# VUE_PIC32_v1_0_PowerOut.net
KiCad netlist of a schematic drawn in Altium Designer
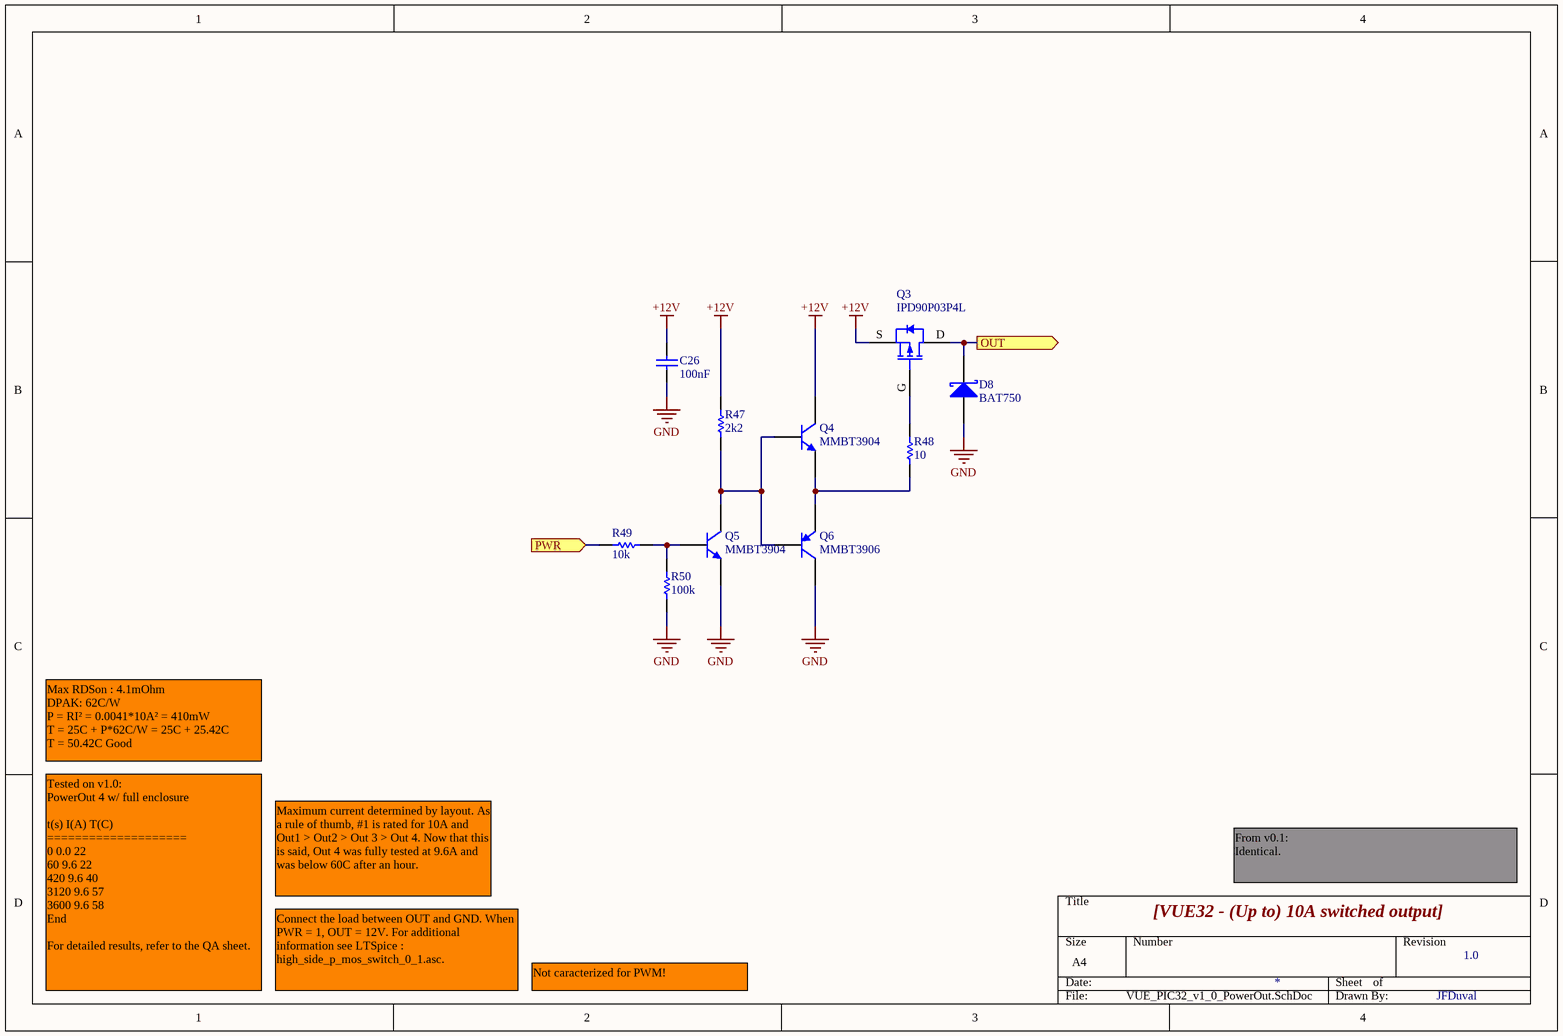
[diagram p0: VUE_PIC32_v1_0_PowerOut.SchDoc]

(export (version "E")
  (design (tool "Eeschema 10.0.6"))
  (components
    (comp (ref "C26")
      (value "100nF")
      (footprint "0402C")
      (description "CAP CER 0.1UF 25V Y5V 0402")
      (fields (field (name "MFG") "TDK") (field (name "MFGPARTNUMBER") "C1005Y5V1E104Z"))
      (libsource (lib "JFD_Cap") (part "CAP_TDK_C_0402_100nF_25V"))
    )
    (comp (ref "D8")
      (value "BAT750")
      (footprint "SOT23-3")
      (description "DIODE SCHOTTKY 40V 750MA SOT23-3")
      (fields (field (name "MFG") "Diodes/Zetex") (field (name "MFGPARTNUMBER") "BAT750TA"))
      (libsource (lib "JFD_Semi") (part "DIODE_DIODESINC_BAT750_SCHOTTKY_SOT23_40V_750MA"))
    )
    (comp (ref "Q3")
      (value "IPD90P03P4L")
      (footprint "TO-252_DPAK")
      (description "MOSFET P-CH 30V 90A TO252-3")
      (fields (field (name "MFG") "Infineon Technologies") (field (name "MFGPARTNUMBER") "IPD90P03P4L-04"))
      (libsource (lib "JFD_Semi") (part "MOSFET_INFINEON_P_CH_IOD90P03P4L_30V_DPAK"))
    )
    (comp (ref "Q4")
      (value "MMBT3904")
      (footprint "SC-75/SOT-416")
      (description "TRANS GP SS NPN 40V SOT416")
      (fields (field (name "MFG") "ON Semiconductor") (field (name "MFGPARTNUMBER") "MMBT3904TT1G"))
      (libsource (lib "JFD_Semi") (part "BJT_ONSEMI_NPN_MMBT3904_40V_200MA_SC75"))
    )
    (comp (ref "Q5")
      (value "MMBT3904")
      (footprint "SC-75/SOT-416")
      (description "TRANS GP SS NPN 40V SOT416")
      (fields (field (name "MFG") "ON Semiconductor") (field (name "MFGPARTNUMBER") "MMBT3904TT1G"))
      (libsource (lib "JFD_Semi") (part "BJT_ONSEMI_NPN_MMBT3904_40V_200MA_SC75"))
    )
    (comp (ref "Q6")
      (value "MMBT3906")
      (footprint "SC-75/SOT-416")
      (description "TRANS PNP GP 40V 200MA SC75-3")
      (fields (field (name "MFG") "ON Semiconductor") (field (name "MFGPARTNUMBER") "MMBT3906TT1G"))
      (libsource (lib "JFD_Semi") (part "BJT_ONSEMI_PNP_MMBT3906_40V_200MA_SC75"))
    )
    (comp (ref "R47")
      (value "2k2")
      (footprint "0402")
      (description "RES 2.20K OHM 1/16W 1% 0402 SMD")
      (fields (field (name "MFG") "Yageo") (field (name "MFGPARTNUMBER") "RC0402FR-072K2L"))
      (libsource (lib "JFD_Res") (part "RES_YAGEO_0402_2K2_1PCT"))
    )
    (comp (ref "R48")
      (value "10")
      (footprint "0402")
      (description "RES 10.0 OHM 1/16W 1% 0402 SMD")
      (fields (field (name "MFG") "Yageo") (field (name "MFGPARTNUMBER") "RC0402FR-0710RL"))
      (libsource (lib "JFD_Res") (part "RES_YAGEO_0402_10_1PCT"))
    )
    (comp (ref "R49")
      (value "10k")
      (footprint "0402")
      (description "RES 10.0K OHM 1/16W 1% 0402 SMD")
      (fields (field (name "MFG") "Yageo") (field (name "MFGPARTNUMBER") "RC0402FR-0710KL"))
      (libsource (lib "JFD_Res") (part "RES_YAGEO_0402_10K_1PCT"))
    )
    (comp (ref "R50")
      (value "100k")
      (footprint "0402")
      (description "RES 100K OHM 1/16W 1% 0402 SMD")
      (fields (field (name "MFG") "Yageo") (field (name "MFGPARTNUMBER") "RC0402FR-07100KL"))
      (libsource (lib "JFD_Res") (part "RES_YAGEO_0402_100K_1PCT"))
    )
  )
  (nets
    (net (code "1") (name "+12V") (class "Default")
      (node (ref "C26") (pin "2") (pinfunction "2_2") (pintype "passive"))
      (node (ref "Q3") (pin "S") (pinfunction "S_S") (pintype "passive"))
      (node (ref "Q4") (pin "3") (pinfunction "C_3") (pintype "passive"))
      (node (ref "R47") (pin "2") (pinfunction "2_2") (pintype "passive"))
    )
    (net (code "2") (name "/OUT") (class "Default")
      (node (ref "D8") (pin "3") (pinfunction "K_3") (pintype "passive"))
      (node (ref "Q3") (pin "D") (pinfunction "D_D") (pintype "passive"))
    )
    (net (code "3") (name "/PWR") (class "Default")
      (node (ref "R49") (pin "1") (pinfunction "1_1") (pintype "passive"))
    )
    (net (code "4") (name "GND") (class "Default")
      (node (ref "C26") (pin "1") (pinfunction "1_1") (pintype "passive"))
      (node (ref "D8") (pin "1") (pinfunction "A_1") (pintype "passive"))
      (node (ref "Q5") (pin "2") (pinfunction "E_2") (pintype "passive"))
      (node (ref "Q6") (pin "3") (pinfunction "C_3") (pintype "passive"))
      (node (ref "R50") (pin "1") (pinfunction "1_1") (pintype "passive"))
    )
    (net (code "5") (name "Net-(Q3-PadG)") (class "Default")
      (node (ref "Q3") (pin "G") (pinfunction "G_G") (pintype "passive"))
      (node (ref "R48") (pin "2") (pinfunction "2_2") (pintype "passive"))
    )
    (net (code "6") (name "Net-(Q4-B)") (class "Default")
      (node (ref "Q4") (pin "1") (pinfunction "B_1") (pintype "passive"))
      (node (ref "Q5") (pin "3") (pinfunction "C_3") (pintype "passive"))
      (node (ref "Q6") (pin "1") (pinfunction "B_1") (pintype "passive"))
      (node (ref "R47") (pin "1") (pinfunction "1_1") (pintype "passive"))
    )
    (net (code "7") (name "Net-(Q4-E)") (class "Default")
      (node (ref "Q4") (pin "2") (pinfunction "E_2") (pintype "passive"))
      (node (ref "Q6") (pin "2") (pinfunction "E_2") (pintype "passive"))
      (node (ref "R48") (pin "1") (pinfunction "1_1") (pintype "passive"))
    )
    (net (code "8") (name "Net-(Q5-B)") (class "Default")
      (node (ref "Q5") (pin "1") (pinfunction "B_1") (pintype "passive"))
      (node (ref "R49") (pin "2") (pinfunction "2_2") (pintype "passive"))
      (node (ref "R50") (pin "2") (pinfunction "2_2") (pintype "passive"))
    )
  )
)
